# nusense-user-io.net
KiCad netlist of a schematic drawn in Altium Designer
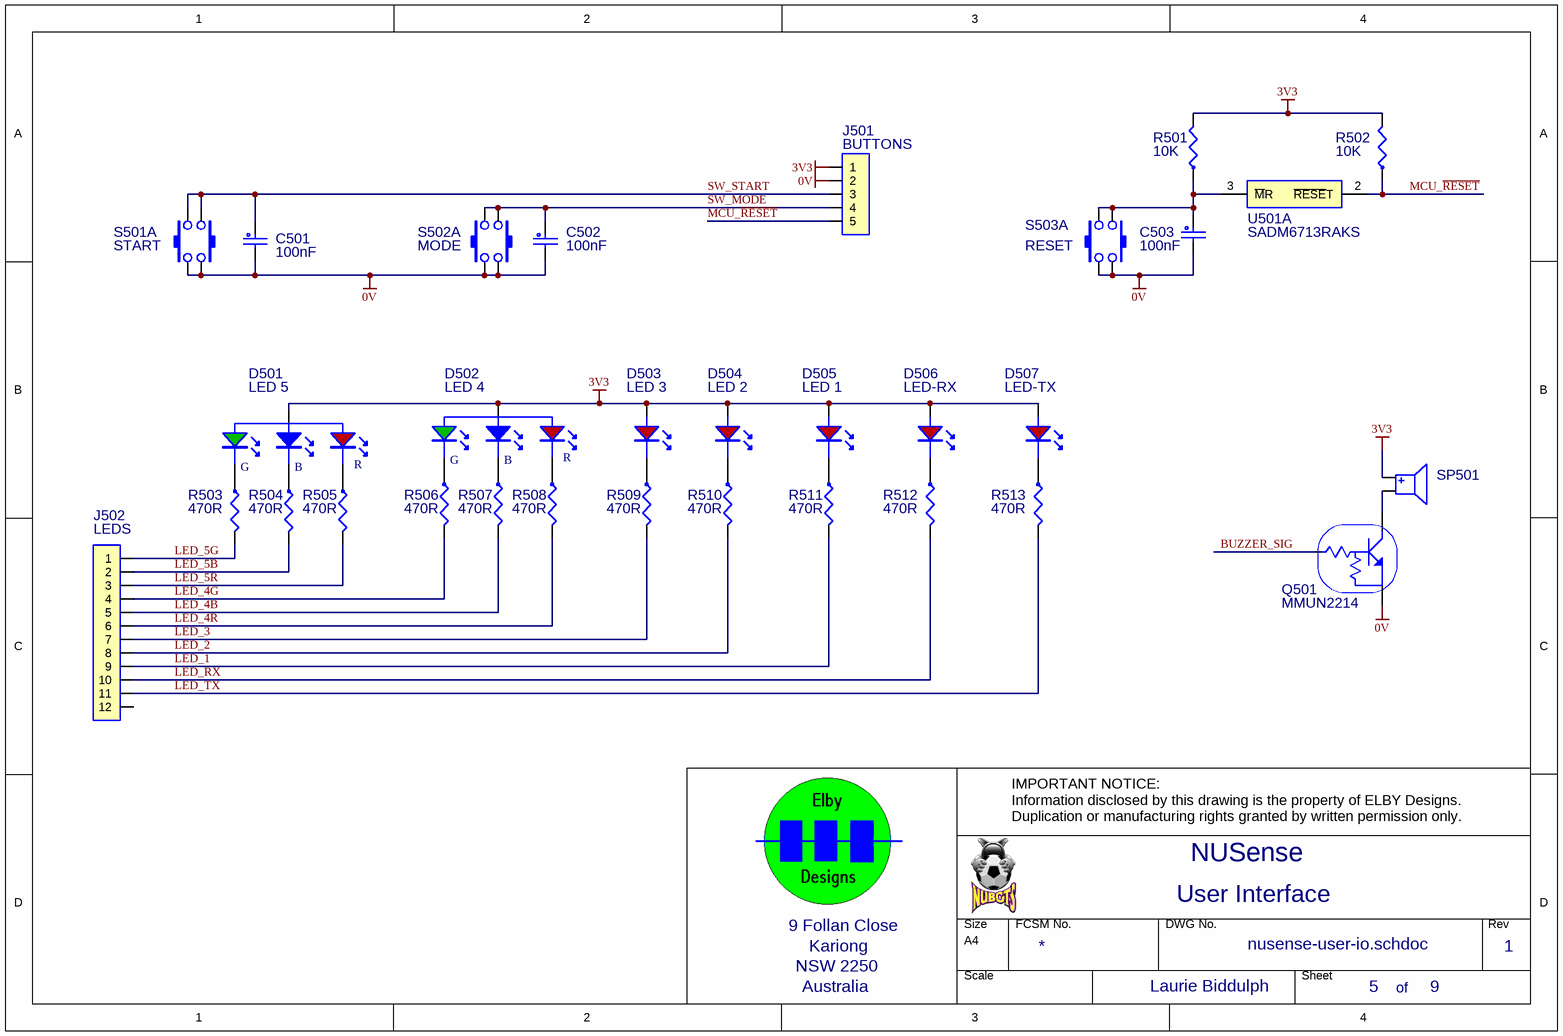
[diagram p0: nusense-user-io.schdoc]

(export (version "E")
  (design (tool "Eeschema 10.0.6"))
  (components
    (comp (ref "C501")
      (value "100nF")
      (footprint "RAD-0.2N(LB)")
      (description "Monolithic Ceramic")
      (libsource (lib "capacitor") (part "CC-100NF(LB)"))
    )
    (comp (ref "C502")
      (value "100nF")
      (footprint "RAD-0.2N(LB)")
      (description "Monolithic Ceramic")
      (libsource (lib "capacitor") (part "CC-100NF(LB)"))
    )
    (comp (ref "C503")
      (value "100nF")
      (footprint "RAD-0.2N(LB)")
      (description "Monolithic Ceramic")
      (libsource (lib "capacitor") (part "CC-100NF(LB)"))
    )
    (comp (ref "D501")
      (value "LED 5")
      (footprint "LED-RGB(LB)")
      (description "RGB LED")
      (libsource (lib "semi") (part "LED-RGB-CA(LB)"))
    )
    (comp (ref "D502")
      (value "LED 4")
      (footprint "LED-RGB(LB)")
      (description "RGB LED")
      (libsource (lib "semi") (part "LED-RGB-CA(LB)"))
    )
    (comp (ref "D503")
      (value "LED 3")
      (footprint "LED-PCB(LB)")
      (description "LED")
      (libsource (lib "semi") (part "LED-RED(LB)"))
    )
    (comp (ref "D504")
      (value "LED 2")
      (footprint "LED-PCB(LB)")
      (description "LED")
      (libsource (lib "semi") (part "LED-RED(LB)"))
    )
    (comp (ref "D505")
      (value "LED 1")
      (footprint "LED-PCB(LB)")
      (description "LED")
      (libsource (lib "semi") (part "LED-RED(LB)"))
    )
    (comp (ref "D506")
      (value "LED-RX")
      (footprint "LED-PCB(LB)")
      (description "LED")
      (libsource (lib "semi") (part "LED-RED(LB)"))
    )
    (comp (ref "D507")
      (value "LED-TX")
      (footprint "LED-PCB(LB)")
      (description "LED")
      (libsource (lib "semi") (part "LED-RED(LB)"))
    )
    (comp (ref "J501")
      (value "BUTTONS")
      (footprint "TERM254-5(LB)")
      (libsource (lib "connectors") (part "CON5(LB)"))
    )
    (comp (ref "J502") (value "LEDS") (libsource (lib "connectors") (part "CON12(LB)")))
    (comp (ref "Q501")
      (value "MMUN2214")
      (footprint "SOT-23(LB)")
      (description "NPN Digital Transistor")
      (libsource (lib "semi") (part "MMUN2214LT1(SMD)"))
    )
    (comp (ref "R501")
      (value "10K")
      (footprint "AXIAL-0.4(LB)")
      (description "0.5W 1% Metal Film Resistor")
      (libsource (lib "resistor") (part "RM-10K(LB)"))
    )
    (comp (ref "R502")
      (value "10K")
      (footprint "AXIAL-0.4(LB)")
      (description "0.5W 1% Metal Film Resistor")
      (libsource (lib "resistor") (part "RM-10K(LB)"))
    )
    (comp (ref "R503")
      (value "470R")
      (footprint "AXIAL-0.4(LB)")
      (description "0.5W 1% Metal Film Resistor")
      (libsource (lib "resistor") (part "RM-470R(LB)"))
    )
    (comp (ref "R504")
      (value "470R")
      (footprint "AXIAL-0.4(LB)")
      (description "0.5W 1% Metal Film Resistor")
      (libsource (lib "resistor") (part "RM-470R(LB)"))
    )
    (comp (ref "R505")
      (value "470R")
      (footprint "AXIAL-0.4(LB)")
      (description "0.5W 1% Metal Film Resistor")
      (libsource (lib "resistor") (part "RM-470R(LB)"))
    )
    (comp (ref "R506")
      (value "470R")
      (footprint "AXIAL-0.4(LB)")
      (description "0.5W 1% Metal Film Resistor")
      (libsource (lib "resistor") (part "RM-470R(LB)"))
    )
    (comp (ref "R507")
      (value "470R")
      (footprint "AXIAL-0.4(LB)")
      (description "0.5W 1% Metal Film Resistor")
      (libsource (lib "resistor") (part "RM-470R(LB)"))
    )
    (comp (ref "R508")
      (value "470R")
      (footprint "AXIAL-0.4(LB)")
      (description "0.5W 1% Metal Film Resistor")
      (libsource (lib "resistor") (part "RM-470R(LB)"))
    )
    (comp (ref "R509")
      (value "470R")
      (footprint "AXIAL-0.4(LB)")
      (description "0.5W 1% Metal Film Resistor")
      (libsource (lib "resistor") (part "RM-470R(LB)"))
    )
    (comp (ref "R510")
      (value "470R")
      (footprint "AXIAL-0.4(LB)")
      (description "0.5W 1% Metal Film Resistor")
      (libsource (lib "resistor") (part "RM-470R(LB)"))
    )
    (comp (ref "R511")
      (value "470R")
      (footprint "AXIAL-0.4(LB)")
      (description "0.5W 1% Metal Film Resistor")
      (libsource (lib "resistor") (part "RM-470R(LB)"))
    )
    (comp (ref "R512")
      (value "470R")
      (footprint "AXIAL-0.4(LB)")
      (description "0.5W 1% Metal Film Resistor")
      (libsource (lib "resistor") (part "RM-470R(LB)"))
    )
    (comp (ref "R513")
      (value "470R")
      (footprint "AXIAL-0.4(LB)")
      (description "0.5W 1% Metal Film Resistor")
      (libsource (lib "resistor") (part "RM-470R(LB)"))
    )
    (comp (ref "S501")
      (value "START")
      (footprint "PCB-PB(LB)")
      (libsource (lib "") (part "SW-PB-DPST(LB)_2"))
    )
    (comp (ref "S502") (value "MODE") (footprint "PCB-PB(LB)") (libsource (lib "") (part "SW-PB-DPST(LB)_2")))
    (comp (ref "S503")
      (value "RESET")
      (footprint "PCB-PB(LB)")
      (libsource (lib "switches") (part "SW-PB-DPST(LB)"))
    )
    (comp (ref "SP501")
      (value "*")
      (footprint "MTA-2V(LB)")
      (libsource (lib "hardware") (part "SPEAKER(LB)"))
    )
    (comp (ref "U501") (value "SADM6713RAKS") (libsource (lib "NuBots") (part "ADM6713")))
  )
  (nets
    (net (code "1") (name "/BUZZER_SIG") (class "Default")
      (node (ref "Q501") (pin "1") (pinfunction "B_1") (pintype "passive"))
    )
    (net (code "2") (name "/LED_1") (class "Default")
      (node (ref "J502") (pin "9") (pinfunction "9_9") (pintype "passive"))
      (node (ref "R511") (pin "2") (pinfunction "2_2") (pintype "passive"))
    )
    (net (code "3") (name "/LED_2") (class "Default")
      (node (ref "J502") (pin "8") (pinfunction "8_8") (pintype "passive"))
      (node (ref "R510") (pin "2") (pinfunction "2_2") (pintype "passive"))
    )
    (net (code "4") (name "/LED_3") (class "Default")
      (node (ref "J502") (pin "7") (pinfunction "7_7") (pintype "passive"))
      (node (ref "R509") (pin "2") (pinfunction "2_2") (pintype "passive"))
    )
    (net (code "5") (name "/LED_4B") (class "Default")
      (node (ref "J502") (pin "5") (pinfunction "5_5") (pintype "passive"))
      (node (ref "R507") (pin "2") (pinfunction "2_2") (pintype "passive"))
    )
    (net (code "6") (name "/LED_4G") (class "Default")
      (node (ref "J502") (pin "4") (pinfunction "4_4") (pintype "passive"))
      (node (ref "R506") (pin "2") (pinfunction "2_2") (pintype "passive"))
    )
    (net (code "7") (name "/LED_4R") (class "Default")
      (node (ref "J502") (pin "6") (pinfunction "6_6") (pintype "passive"))
      (node (ref "R508") (pin "2") (pinfunction "2_2") (pintype "passive"))
    )
    (net (code "8") (name "/LED_5B") (class "Default")
      (node (ref "J502") (pin "2") (pinfunction "2_2") (pintype "passive"))
      (node (ref "R504") (pin "2") (pinfunction "2_2") (pintype "passive"))
    )
    (net (code "9") (name "/LED_5G") (class "Default")
      (node (ref "J502") (pin "1") (pinfunction "1_1") (pintype "passive"))
      (node (ref "R503") (pin "2") (pinfunction "2_2") (pintype "passive"))
    )
    (net (code "10") (name "/LED_5R") (class "Default")
      (node (ref "J502") (pin "3") (pinfunction "3_3") (pintype "passive"))
      (node (ref "R505") (pin "2") (pinfunction "2_2") (pintype "passive"))
    )
    (net (code "11") (name "/LED_RX") (class "Default")
      (node (ref "J502") (pin "10") (pinfunction "10_10") (pintype "passive"))
      (node (ref "R512") (pin "2") (pinfunction "2_2") (pintype "passive"))
    )
    (net (code "12") (name "/LED_TX") (class "Default")
      (node (ref "J502") (pin "11") (pinfunction "11_11") (pintype "passive"))
      (node (ref "R513") (pin "2") (pinfunction "2_2") (pintype "passive"))
    )
    (net (code "13") (name "/MCU_~{RESET}") (class "Default")
      (node (ref "J501") (pin "5") (pinfunction "5_5") (pintype "passive"))
      (node (ref "R502") (pin "1") (pinfunction "1_1") (pintype "passive"))
      (node (ref "U501") (pin "2") (pinfunction "~{RESE}T_2") (pintype "passive"))
    )
    (net (code "14") (name "/SW_MODE") (class "Default")
      (node (ref "C502") (pin "1") (pintype "passive"))
      (node (ref "J501") (pin "4") (pinfunction "4_4") (pintype "passive"))
      (node (ref "S502") (pin "2") (pinfunction "NO_2") (pintype "passive"))
      (node (ref "S502") (pin "4") (pinfunction "NO_4") (pintype "passive"))
    )
    (net (code "15") (name "/SW_START") (class "Default")
      (node (ref "C501") (pin "1") (pintype "passive"))
      (node (ref "J501") (pin "3") (pinfunction "3_3") (pintype "passive"))
      (node (ref "S501") (pin "2") (pinfunction "NO_2") (pintype "passive"))
      (node (ref "S501") (pin "4") (pinfunction "NO_4") (pintype "passive"))
    )
    (net (code "16") (name "0V") (class "Default")
      (node (ref "C501") (pin "2") (pintype "passive"))
      (node (ref "C502") (pin "2") (pintype "passive"))
      (node (ref "C503") (pin "2") (pintype "passive"))
      (node (ref "J501") (pin "2") (pinfunction "2_2") (pintype "passive"))
      (node (ref "Q501") (pin "2") (pinfunction "E_2") (pintype "passive"))
      (node (ref "S501") (pin "1") (pinfunction "COM_1") (pintype "passive"))
      (node (ref "S501") (pin "3") (pinfunction "COM_3") (pintype "passive"))
      (node (ref "S502") (pin "1") (pinfunction "COM_1") (pintype "passive"))
      (node (ref "S502") (pin "3") (pinfunction "COM_3") (pintype "passive"))
      (node (ref "S503") (pin "1") (pinfunction "COM_1") (pintype "passive"))
      (node (ref "S503") (pin "3") (pinfunction "COM_3") (pintype "passive"))
    )
    (net (code "17") (name "3V3") (class "Default")
      (node (ref "D501") (pin "1") (pinfunction "A_1") (pintype "passive"))
      (node (ref "D502") (pin "1") (pinfunction "A_1") (pintype "passive"))
      (node (ref "D503") (pin "A") (pinfunction "A_A") (pintype "passive"))
      (node (ref "D504") (pin "A") (pinfunction "A_A") (pintype "passive"))
      (node (ref "D505") (pin "A") (pinfunction "A_A") (pintype "passive"))
      (node (ref "D506") (pin "A") (pinfunction "A_A") (pintype "passive"))
      (node (ref "D507") (pin "A") (pinfunction "A_A") (pintype "passive"))
      (node (ref "J501") (pin "1") (pinfunction "1_1") (pintype "passive"))
      (node (ref "R501") (pin "2") (pinfunction "2_2") (pintype "passive"))
      (node (ref "R502") (pin "2") (pinfunction "2_2") (pintype "passive"))
      (node (ref "SP501") (pin "1") (pinfunction "1_1") (pintype "passive"))
    )
    (net (code "18") (name "Net-(D501-KB)") (class "Default")
      (node (ref "D501") (pin "3") (pinfunction "KB_3") (pintype "passive"))
      (node (ref "R504") (pin "1") (pinfunction "1_1") (pintype "passive"))
    )
    (net (code "19") (name "Net-(D501-KG)") (class "Default")
      (node (ref "D501") (pin "2") (pinfunction "KG_2") (pintype "passive"))
      (node (ref "R503") (pin "1") (pinfunction "1_1") (pintype "passive"))
    )
    (net (code "20") (name "Net-(D501-KR)") (class "Default")
      (node (ref "D501") (pin "4") (pinfunction "KR_4") (pintype "passive"))
      (node (ref "R505") (pin "1") (pinfunction "1_1") (pintype "passive"))
    )
    (net (code "21") (name "Net-(D502-KB)") (class "Default")
      (node (ref "D502") (pin "3") (pinfunction "KB_3") (pintype "passive"))
      (node (ref "R507") (pin "1") (pinfunction "1_1") (pintype "passive"))
    )
    (net (code "22") (name "Net-(D502-KG)") (class "Default")
      (node (ref "D502") (pin "2") (pinfunction "KG_2") (pintype "passive"))
      (node (ref "R506") (pin "1") (pinfunction "1_1") (pintype "passive"))
    )
    (net (code "23") (name "Net-(D502-KR)") (class "Default")
      (node (ref "D502") (pin "4") (pinfunction "KR_4") (pintype "passive"))
      (node (ref "R508") (pin "1") (pinfunction "1_1") (pintype "passive"))
    )
    (net (code "24") (name "Net-(D503-PadK)") (class "Default")
      (node (ref "D503") (pin "K") (pinfunction "K_K") (pintype "passive"))
      (node (ref "R509") (pin "1") (pinfunction "1_1") (pintype "passive"))
    )
    (net (code "25") (name "Net-(D504-PadK)") (class "Default")
      (node (ref "D504") (pin "K") (pinfunction "K_K") (pintype "passive"))
      (node (ref "R510") (pin "1") (pinfunction "1_1") (pintype "passive"))
    )
    (net (code "26") (name "Net-(D505-PadK)") (class "Default")
      (node (ref "D505") (pin "K") (pinfunction "K_K") (pintype "passive"))
      (node (ref "R511") (pin "1") (pinfunction "1_1") (pintype "passive"))
    )
    (net (code "27") (name "Net-(D506-PadK)") (class "Default")
      (node (ref "D506") (pin "K") (pinfunction "K_K") (pintype "passive"))
      (node (ref "R512") (pin "1") (pinfunction "1_1") (pintype "passive"))
    )
    (net (code "28") (name "Net-(D507-PadK)") (class "Default")
      (node (ref "D507") (pin "K") (pinfunction "K_K") (pintype "passive"))
      (node (ref "R513") (pin "1") (pinfunction "1_1") (pintype "passive"))
    )
    (net (code "29") (name "Net-(Q501-C)") (class "Default")
      (node (ref "Q501") (pin "3") (pinfunction "C_3") (pintype "passive"))
      (node (ref "SP501") (pin "2") (pinfunction "2_2") (pintype "passive"))
    )
    (net (code "30") (name "Net-(S503A-NO)") (class "Default")
      (node (ref "C503") (pin "1") (pintype "passive"))
      (node (ref "R501") (pin "1") (pinfunction "1_1") (pintype "passive"))
      (node (ref "S503") (pin "2") (pinfunction "NO_2") (pintype "passive"))
      (node (ref "S503") (pin "4") (pinfunction "NO_4") (pintype "passive"))
      (node (ref "U501") (pin "3") (pinfunction "~{M}R_3") (pintype "passive"))
    )
    (net (code "31") (name "unconnected-(J502-Pad12)") (class "Default")
      (node (ref "J502") (pin "12") (pinfunction "12_12") (pintype "passive"))
    )
  )
)
